# LEDs.net
KiCad netlist of a schematic drawn in Altium Designer
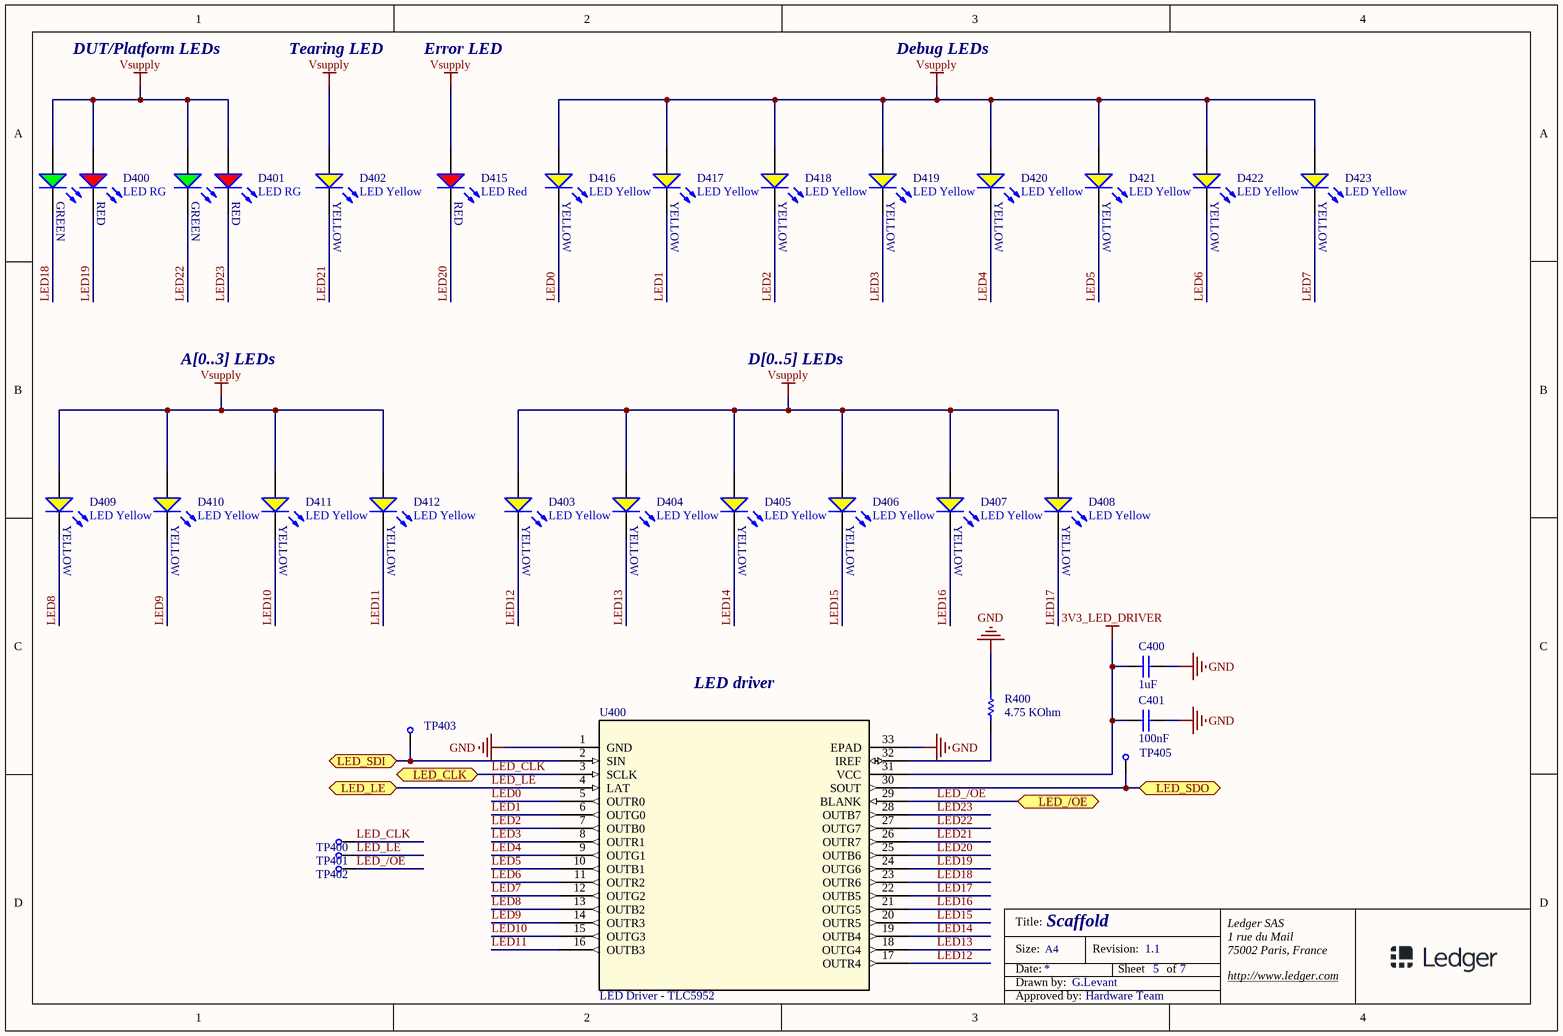
[diagram p0: LEDs.SchDoc]

(export (version "E")
  (design (tool "Eeschema 10.0.6"))
  (components
    (comp (ref "C400")
      (value "1uF")
      (footprint "CAP0603")
      (description "Capacitor 0603 - 1uF - 16V - X7R - 10%")
      (fields (field (name "MANUFACTURER") "Kemet") (field (name "POWER") "16V"))
      (libsource (lib "Ledger_Prod") (part "Capacitor 0603 -     1uF - 16V - X7R - 10%"))
    )
    (comp (ref "C401")
      (value "100nF")
      (footprint "CAP0603")
      (description "Capacitor 0603 - 100nF - 16V - X7R - 10%")
      (fields (field (name "POWER") "16V") (field (name "TOLERANCE") "10%"))
      (libsource (lib "Ledger_Prod") (part "Capacitor 0603 - 100nF - 16V - X7R - 10%"))
    )
    (comp (ref "D400")
      (value "LED RG")
      (footprint "PLCC-4_3528")
      (description "Opto - DEL - RG 630/572nm 250/60 mcd - 20mA")
      (fields (field (name "MANUFACTURER") "Wurth"))
      (libsource (lib "Ledger_Prod") (part "Opto - DEL - RG 630/572nm 250/60 mcd - 20mA"))
    )
    (comp (ref "D401")
      (value "LED RG")
      (footprint "PLCC-4_3528")
      (description "Opto - DEL - RG 630/572nm 250/60 mcd - 20mA")
      (fields (field (name "MANUFACTURER") "Wurth"))
      (libsource (lib "Ledger_Prod") (part "Opto - DEL - RG 630/572nm 250/60 mcd - 20mA"))
    )
    (comp (ref "D402")
      (value "LED Yellow")
      (footprint "KINGBRIGHT_AA3528")
      (description "Opto - DEL - Yellow 590nm - 2mA -30 mcd")
      (fields (field (name "MANUFACTURER") "Kingbright"))
      (libsource (lib "Ledger_Prod") (part "Opto - DEL - Yellow 590nm - 2mA -30 mcd"))
    )
    (comp (ref "D403")
      (value "LED Yellow")
      (footprint "KINGBRIGHT_AA3528")
      (description "Opto - DEL - Yellow 590nm - 2mA -30 mcd")
      (fields (field (name "MANUFACTURER") "Kingbright"))
      (libsource (lib "Ledger_Prod") (part "Opto - DEL - Yellow 590nm - 2mA -30 mcd"))
    )
    (comp (ref "D404")
      (value "LED Yellow")
      (footprint "KINGBRIGHT_AA3528")
      (description "Opto - DEL - Yellow 590nm - 2mA -30 mcd")
      (fields (field (name "MANUFACTURER") "Kingbright"))
      (libsource (lib "Ledger_Prod") (part "Opto - DEL - Yellow 590nm - 2mA -30 mcd"))
    )
    (comp (ref "D405")
      (value "LED Yellow")
      (footprint "KINGBRIGHT_AA3528")
      (description "Opto - DEL - Yellow 590nm - 2mA -30 mcd")
      (fields (field (name "MANUFACTURER") "Kingbright"))
      (libsource (lib "Ledger_Prod") (part "Opto - DEL - Yellow 590nm - 2mA -30 mcd"))
    )
    (comp (ref "D406")
      (value "LED Yellow")
      (footprint "KINGBRIGHT_AA3528")
      (description "Opto - DEL - Yellow 590nm - 2mA -30 mcd")
      (fields (field (name "MANUFACTURER") "Kingbright"))
      (libsource (lib "Ledger_Prod") (part "Opto - DEL - Yellow 590nm - 2mA -30 mcd"))
    )
    (comp (ref "D407")
      (value "LED Yellow")
      (footprint "KINGBRIGHT_AA3528")
      (description "Opto - DEL - Yellow 590nm - 2mA -30 mcd")
      (fields (field (name "MANUFACTURER") "Kingbright"))
      (libsource (lib "Ledger_Prod") (part "Opto - DEL - Yellow 590nm - 2mA -30 mcd"))
    )
    (comp (ref "D408")
      (value "LED Yellow")
      (footprint "KINGBRIGHT_AA3528")
      (description "Opto - DEL - Yellow 590nm - 2mA -30 mcd")
      (fields (field (name "MANUFACTURER") "Kingbright"))
      (libsource (lib "Ledger_Prod") (part "Opto - DEL - Yellow 590nm - 2mA -30 mcd"))
    )
    (comp (ref "D409")
      (value "LED Yellow")
      (footprint "KINGBRIGHT_AA3528")
      (description "Opto - DEL - Yellow 590nm - 2mA -30 mcd")
      (fields (field (name "MANUFACTURER") "Kingbright"))
      (libsource (lib "Ledger_Prod") (part "Opto - DEL - Yellow 590nm - 2mA -30 mcd"))
    )
    (comp (ref "D410")
      (value "LED Yellow")
      (footprint "KINGBRIGHT_AA3528")
      (description "Opto - DEL - Yellow 590nm - 2mA -30 mcd")
      (fields (field (name "MANUFACTURER") "Kingbright"))
      (libsource (lib "Ledger_Prod") (part "Opto - DEL - Yellow 590nm - 2mA -30 mcd"))
    )
    (comp (ref "D411")
      (value "LED Yellow")
      (footprint "KINGBRIGHT_AA3528")
      (description "Opto - DEL - Yellow 590nm - 2mA -30 mcd")
      (fields (field (name "MANUFACTURER") "Kingbright"))
      (libsource (lib "Ledger_Prod") (part "Opto - DEL - Yellow 590nm - 2mA -30 mcd"))
    )
    (comp (ref "D412")
      (value "LED Yellow")
      (footprint "KINGBRIGHT_AA3528")
      (description "Opto - DEL - Yellow 590nm - 2mA -30 mcd")
      (fields (field (name "MANUFACTURER") "Kingbright"))
      (libsource (lib "Ledger_Prod") (part "Opto - DEL - Yellow 590nm - 2mA -30 mcd"))
    )
    (comp (ref "D415")
      (value "LED Red")
      (footprint "KINGBRIGHT_AA3528")
      (description "Opto - DEL - Red 625nm - 2mA -120 mcd")
      (fields (field (name "MANUFACTURER") "Kingbright"))
      (libsource (lib "Ledger_Prod") (part "Opto - DEL - Red 625nm - 2mA -120 mcd"))
    )
    (comp (ref "D416")
      (value "LED Yellow")
      (footprint "KINGBRIGHT_AA3528")
      (description "Opto - DEL - Yellow 590nm - 2mA -30 mcd")
      (fields (field (name "MANUFACTURER") "Kingbright"))
      (libsource (lib "Ledger_Prod") (part "Opto - DEL - Yellow 590nm - 2mA -30 mcd"))
    )
    (comp (ref "D417")
      (value "LED Yellow")
      (footprint "KINGBRIGHT_AA3528")
      (description "Opto - DEL - Yellow 590nm - 2mA -30 mcd")
      (fields (field (name "MANUFACTURER") "Kingbright"))
      (libsource (lib "Ledger_Prod") (part "Opto - DEL - Yellow 590nm - 2mA -30 mcd"))
    )
    (comp (ref "D418")
      (value "LED Yellow")
      (footprint "KINGBRIGHT_AA3528")
      (description "Opto - DEL - Yellow 590nm - 2mA -30 mcd")
      (fields (field (name "MANUFACTURER") "Kingbright"))
      (libsource (lib "Ledger_Prod") (part "Opto - DEL - Yellow 590nm - 2mA -30 mcd"))
    )
    (comp (ref "D419")
      (value "LED Yellow")
      (footprint "KINGBRIGHT_AA3528")
      (description "Opto - DEL - Yellow 590nm - 2mA -30 mcd")
      (fields (field (name "MANUFACTURER") "Kingbright"))
      (libsource (lib "Ledger_Prod") (part "Opto - DEL - Yellow 590nm - 2mA -30 mcd"))
    )
    (comp (ref "D420")
      (value "LED Yellow")
      (footprint "KINGBRIGHT_AA3528")
      (description "Opto - DEL - Yellow 590nm - 2mA -30 mcd")
      (fields (field (name "MANUFACTURER") "Kingbright"))
      (libsource (lib "Ledger_Prod") (part "Opto - DEL - Yellow 590nm - 2mA -30 mcd"))
    )
    (comp (ref "D421")
      (value "LED Yellow")
      (footprint "KINGBRIGHT_AA3528")
      (description "Opto - DEL - Yellow 590nm - 2mA -30 mcd")
      (fields (field (name "MANUFACTURER") "Kingbright"))
      (libsource (lib "Ledger_Prod") (part "Opto - DEL - Yellow 590nm - 2mA -30 mcd"))
    )
    (comp (ref "D422")
      (value "LED Yellow")
      (footprint "KINGBRIGHT_AA3528")
      (description "Opto - DEL - Yellow 590nm - 2mA -30 mcd")
      (fields (field (name "MANUFACTURER") "Kingbright"))
      (libsource (lib "Ledger_Prod") (part "Opto - DEL - Yellow 590nm - 2mA -30 mcd"))
    )
    (comp (ref "D423")
      (value "LED Yellow")
      (footprint "KINGBRIGHT_AA3528")
      (description "Opto - DEL - Yellow 590nm - 2mA -30 mcd")
      (fields (field (name "MANUFACTURER") "Kingbright"))
      (libsource (lib "Ledger_Prod") (part "Opto - DEL - Yellow 590nm - 2mA -30 mcd"))
    )
    (comp (ref "R400")
      (value "4.75 KOhm")
      (footprint "RES0603")
      (description "Resistor 0603 - 4.75KOhm - 1/10W - 1%")
      (fields (field (name "TOLERANCE") "1%") (field (name "POWER") "1/10W"))
      (libsource (lib "Ledger_Prod") (part "Resistor 0603 - 4.75KOhm - 1/10W - 1%"))
    )
    (comp (ref "TP400")
      (value "~")
      (footprint "TP_001")
      (description "Misc - Test point CMS")
      (libsource (lib "Ledger_Dev") (part "Misc - Test point CMS"))
    )
    (comp (ref "TP401")
      (value "~")
      (footprint "TP_001")
      (description "Misc - Test point CMS")
      (libsource (lib "Ledger_Dev") (part "Misc - Test point CMS"))
    )
    (comp (ref "TP402")
      (value "~")
      (footprint "TP_001")
      (description "Misc - Test point CMS")
      (libsource (lib "Ledger_Dev") (part "Misc - Test point CMS"))
    )
    (comp (ref "TP403")
      (value "~")
      (footprint "TP_001")
      (description "Misc - Test point CMS")
      (libsource (lib "Ledger_Dev") (part "Misc - Test point CMS"))
    )
    (comp (ref "TP405")
      (value "~")
      (footprint "TP_001")
      (description "Misc - Test point CMS")
      (libsource (lib "Ledger_Dev") (part "Misc - Test point CMS"))
    )
    (comp (ref "U400")
      (value "LED Driver - TLC5952")
      (footprint "HTSSOP32")
      (description "Power - LED Driver - 24 LEDs - TLC5952 -  HTSSOP32")
      (fields (field (name "MANUFACTURER") "Texas Instruments"))
      (libsource (lib "Ledger_Dev") (part "Power - LED Driver - 24 LEDs - TLC5952 -  HTSSOP32"))
    )
  )
  (nets
    (net (code "1") (name "/LED0") (class "Default")
      (node (ref "D416") (pin "1") (pinfunction "K_1") (pintype "passive"))
      (node (ref "U400") (pin "5") (pinfunction "OUTR0_5") (pintype "output"))
    )
    (net (code "2") (name "/LED1") (class "Default")
      (node (ref "D417") (pin "1") (pinfunction "K_1") (pintype "passive"))
      (node (ref "U400") (pin "6") (pinfunction "OUTG0_6") (pintype "output"))
    )
    (net (code "3") (name "/LED2") (class "Default")
      (node (ref "D418") (pin "1") (pinfunction "K_1") (pintype "passive"))
      (node (ref "U400") (pin "7") (pinfunction "OUTB0_7") (pintype "output"))
    )
    (net (code "4") (name "/LED3") (class "Default")
      (node (ref "D419") (pin "1") (pinfunction "K_1") (pintype "passive"))
      (node (ref "U400") (pin "8") (pinfunction "OUTR1_8") (pintype "output"))
    )
    (net (code "5") (name "/LED4") (class "Default")
      (node (ref "D420") (pin "1") (pinfunction "K_1") (pintype "passive"))
      (node (ref "U400") (pin "9") (pinfunction "OUTG1_9") (pintype "output"))
    )
    (net (code "6") (name "/LED5") (class "Default")
      (node (ref "D421") (pin "1") (pinfunction "K_1") (pintype "passive"))
      (node (ref "U400") (pin "10") (pinfunction "OUTB1_10") (pintype "output"))
    )
    (net (code "7") (name "/LED6") (class "Default")
      (node (ref "D422") (pin "1") (pinfunction "K_1") (pintype "passive"))
      (node (ref "U400") (pin "11") (pinfunction "OUTR2_11") (pintype "output"))
    )
    (net (code "8") (name "/LED7") (class "Default")
      (node (ref "D423") (pin "1") (pinfunction "K_1") (pintype "passive"))
      (node (ref "U400") (pin "12") (pinfunction "OUTG2_12") (pintype "output"))
    )
    (net (code "9") (name "/LED8") (class "Default")
      (node (ref "D409") (pin "1") (pinfunction "K_1") (pintype "passive"))
      (node (ref "U400") (pin "13") (pinfunction "OUTB2_13") (pintype "output"))
    )
    (net (code "10") (name "/LED9") (class "Default")
      (node (ref "D410") (pin "1") (pinfunction "K_1") (pintype "passive"))
      (node (ref "U400") (pin "14") (pinfunction "OUTR3_14") (pintype "output"))
    )
    (net (code "11") (name "/LED10") (class "Default")
      (node (ref "D411") (pin "1") (pinfunction "K_1") (pintype "passive"))
      (node (ref "U400") (pin "15") (pinfunction "OUTG3_15") (pintype "output"))
    )
    (net (code "12") (name "/LED11") (class "Default")
      (node (ref "D412") (pin "1") (pinfunction "K_1") (pintype "passive"))
      (node (ref "U400") (pin "16") (pinfunction "OUTB3_16") (pintype "output"))
    )
    (net (code "13") (name "/LED12") (class "Default")
      (node (ref "D403") (pin "1") (pinfunction "K_1") (pintype "passive"))
      (node (ref "U400") (pin "17") (pinfunction "OUTR4_17") (pintype "output"))
    )
    (net (code "14") (name "/LED13") (class "Default")
      (node (ref "D404") (pin "1") (pinfunction "K_1") (pintype "passive"))
      (node (ref "U400") (pin "18") (pinfunction "OUTG4_18") (pintype "output"))
    )
    (net (code "15") (name "/LED14") (class "Default")
      (node (ref "D405") (pin "1") (pinfunction "K_1") (pintype "passive"))
      (node (ref "U400") (pin "19") (pinfunction "OUTB4_19") (pintype "output"))
    )
    (net (code "16") (name "/LED15") (class "Default")
      (node (ref "D406") (pin "1") (pinfunction "K_1") (pintype "passive"))
      (node (ref "U400") (pin "20") (pinfunction "OUTR5_20") (pintype "output"))
    )
    (net (code "17") (name "/LED16") (class "Default")
      (node (ref "D407") (pin "1") (pinfunction "K_1") (pintype "passive"))
      (node (ref "U400") (pin "21") (pinfunction "OUTG5_21") (pintype "output"))
    )
    (net (code "18") (name "/LED17") (class "Default")
      (node (ref "D408") (pin "1") (pinfunction "K_1") (pintype "passive"))
      (node (ref "U400") (pin "22") (pinfunction "OUTB5_22") (pintype "output"))
    )
    (net (code "19") (name "/LED18") (class "Default")
      (node (ref "D400") (pin "4") (pinfunction "KG_4") (pintype "passive"))
      (node (ref "U400") (pin "23") (pinfunction "OUTR6_23") (pintype "output"))
    )
    (net (code "20") (name "/LED19") (class "Default")
      (node (ref "D400") (pin "3") (pinfunction "KR_3") (pintype "passive"))
      (node (ref "U400") (pin "24") (pinfunction "OUTG6_24") (pintype "output"))
    )
    (net (code "21") (name "/LED20") (class "Default")
      (node (ref "D415") (pin "1") (pinfunction "K_1") (pintype "passive"))
      (node (ref "U400") (pin "25") (pinfunction "OUTB6_25") (pintype "output"))
    )
    (net (code "22") (name "/LED21") (class "Default")
      (node (ref "D402") (pin "1") (pinfunction "K_1") (pintype "passive"))
      (node (ref "U400") (pin "26") (pinfunction "OUTR7_26") (pintype "output"))
    )
    (net (code "23") (name "/LED22") (class "Default")
      (node (ref "D401") (pin "4") (pinfunction "KG_4") (pintype "passive"))
      (node (ref "U400") (pin "27") (pinfunction "OUTG7_27") (pintype "output"))
    )
    (net (code "24") (name "/LED23") (class "Default")
      (node (ref "D401") (pin "3") (pinfunction "KR_3") (pintype "passive"))
      (node (ref "U400") (pin "28") (pinfunction "OUTB7_28") (pintype "output"))
    )
    (net (code "25") (name "/LED_CLK") (class "Default")
      (node (ref "TP400") (pin "1") (pinfunction "1_1") (pintype "passive"))
      (node (ref "U400") (pin "3") (pinfunction "SCLK_3") (pintype "input"))
    )
    (net (code "26") (name "/LED_LE") (class "Default")
      (node (ref "TP401") (pin "1") (pinfunction "1_1") (pintype "passive"))
      (node (ref "U400") (pin "4") (pinfunction "LAT_4") (pintype "input"))
    )
    (net (code "27") (name "/LED_SDI") (class "Default")
      (node (ref "TP403") (pin "1") (pinfunction "1_1") (pintype "passive"))
      (node (ref "U400") (pin "2") (pinfunction "SIN_2") (pintype "input"))
    )
    (net (code "28") (name "/LED_SDO") (class "Default")
      (node (ref "TP405") (pin "1") (pinfunction "1_1") (pintype "passive"))
      (node (ref "U400") (pin "30") (pinfunction "SOUT_30") (pintype "output"))
    )
    (net (code "29") (name "/LED_{slash}OE") (class "Default")
      (node (ref "TP402") (pin "1") (pinfunction "1_1") (pintype "passive"))
      (node (ref "U400") (pin "29") (pinfunction "BLANK_29") (pintype "input"))
    )
    (net (code "30") (name "3V3_LED_DRIVER") (class "Default")
      (node (ref "C400") (pin "1") (pinfunction "1_1") (pintype "passive"))
      (node (ref "C401") (pin "1") (pinfunction "1_1") (pintype "passive"))
      (node (ref "U400") (pin "31") (pinfunction "VCC_31") (pintype "power_in"))
    )
    (net (code "31") (name "GND") (class "Default")
      (node (ref "C400") (pin "2") (pinfunction "2_2") (pintype "passive"))
      (node (ref "C401") (pin "2") (pinfunction "2_2") (pintype "passive"))
      (node (ref "R400") (pin "2") (pinfunction "2_2") (pintype "passive"))
      (node (ref "U400") (pin "1") (pinfunction "GND_1") (pintype "power_in"))
      (node (ref "U400") (pin "33") (pinfunction "EPAD_33") (pintype "passive"))
    )
    (net (code "32") (name "Net-(U400-IREF)") (class "Default")
      (node (ref "R400") (pin "1") (pinfunction "1_1") (pintype "passive"))
      (node (ref "U400") (pin "32") (pinfunction "IREF_32") (pintype "bidirectional"))
    )
    (net (code "33") (name "Vsupply") (class "Default")
      (node (ref "D400") (pin "1") (pinfunction "AR_1") (pintype "passive"))
      (node (ref "D400") (pin "2") (pinfunction "AG_2") (pintype "passive"))
      (node (ref "D401") (pin "1") (pinfunction "AR_1") (pintype "passive"))
      (node (ref "D401") (pin "2") (pinfunction "AG_2") (pintype "passive"))
      (node (ref "D402") (pin "2") (pinfunction "A_2") (pintype "passive"))
      (node (ref "D403") (pin "2") (pinfunction "A_2") (pintype "passive"))
      (node (ref "D404") (pin "2") (pinfunction "A_2") (pintype "passive"))
      (node (ref "D405") (pin "2") (pinfunction "A_2") (pintype "passive"))
      (node (ref "D406") (pin "2") (pinfunction "A_2") (pintype "passive"))
      (node (ref "D407") (pin "2") (pinfunction "A_2") (pintype "passive"))
      (node (ref "D408") (pin "2") (pinfunction "A_2") (pintype "passive"))
      (node (ref "D409") (pin "2") (pinfunction "A_2") (pintype "passive"))
      (node (ref "D410") (pin "2") (pinfunction "A_2") (pintype "passive"))
      (node (ref "D411") (pin "2") (pinfunction "A_2") (pintype "passive"))
      (node (ref "D412") (pin "2") (pinfunction "A_2") (pintype "passive"))
      (node (ref "D415") (pin "2") (pinfunction "A_2") (pintype "passive"))
      (node (ref "D416") (pin "2") (pinfunction "A_2") (pintype "passive"))
      (node (ref "D417") (pin "2") (pinfunction "A_2") (pintype "passive"))
      (node (ref "D418") (pin "2") (pinfunction "A_2") (pintype "passive"))
      (node (ref "D419") (pin "2") (pinfunction "A_2") (pintype "passive"))
      (node (ref "D420") (pin "2") (pinfunction "A_2") (pintype "passive"))
      (node (ref "D421") (pin "2") (pinfunction "A_2") (pintype "passive"))
      (node (ref "D422") (pin "2") (pinfunction "A_2") (pintype "passive"))
      (node (ref "D423") (pin "2") (pinfunction "A_2") (pintype "passive"))
    )
  )
)
